# mkstepper.net
KiCad netlist of a schematic drawn in EAGLE
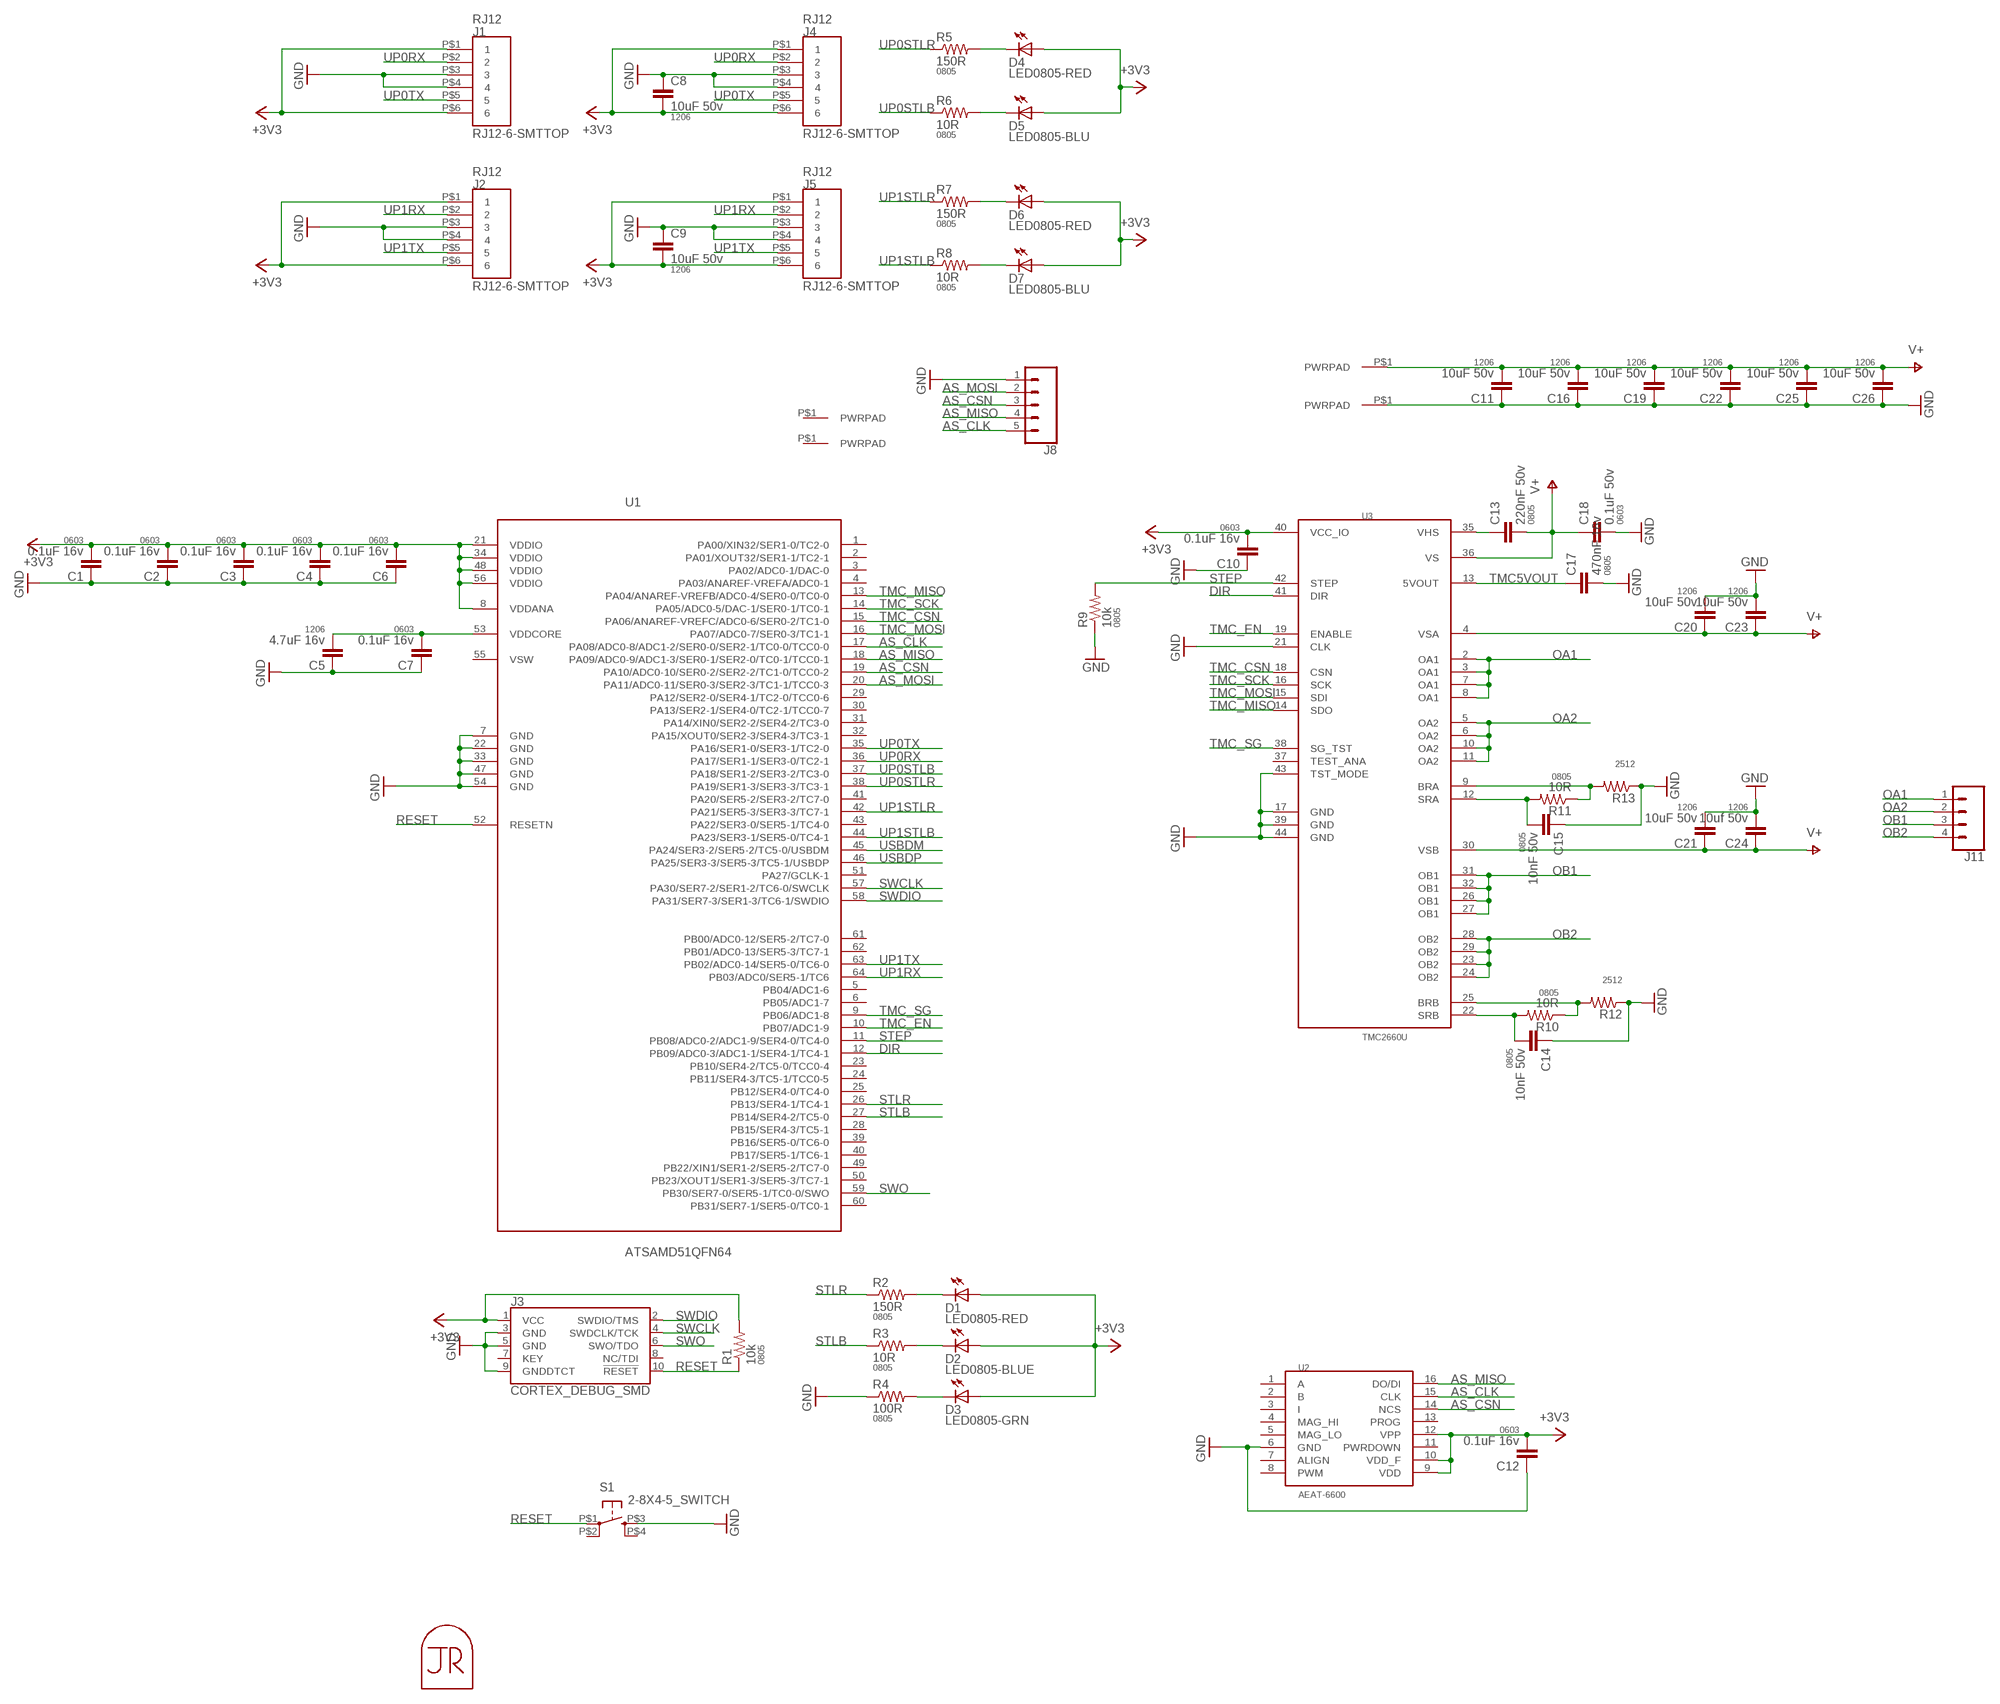
[diagram p0: schematic, sheet 1]

(export (version "E")
  (design (tool "Eeschema 10.0.6"))
  (components
    (comp (ref "C1")
      (value "0.1uF 16v")
      (footprint "eagle-import:0603-CAP")
      (libsource (lib "eagle-import") (part "CAP0603-CAP"))
    )
    (comp (ref "C2")
      (value "0.1uF 16v")
      (footprint "eagle-import:0603-CAP")
      (libsource (lib "eagle-import") (part "CAP0603-CAP"))
    )
    (comp (ref "C3")
      (value "0.1uF 16v")
      (footprint "eagle-import:0603-CAP")
      (libsource (lib "eagle-import") (part "CAP0603-CAP"))
    )
    (comp (ref "C4")
      (value "0.1uF 16v")
      (footprint "eagle-import:0603-CAP")
      (libsource (lib "eagle-import") (part "CAP0603-CAP"))
    )
    (comp (ref "C5")
      (value "4.7uF 16v")
      (footprint "eagle-import:1206")
      (libsource (lib "eagle-import") (part "CAP1206"))
    )
    (comp (ref "C6")
      (value "0.1uF 16v")
      (footprint "eagle-import:0603-CAP")
      (libsource (lib "eagle-import") (part "CAP0603-CAP"))
    )
    (comp (ref "C7")
      (value "0.1uF 16v")
      (footprint "eagle-import:0603-CAP")
      (libsource (lib "eagle-import") (part "CAP0603-CAP"))
    )
    (comp (ref "C8")
      (value "10uF 50v")
      (footprint "eagle-import:1206")
      (libsource (lib "eagle-import") (part "CAP1206"))
    )
    (comp (ref "C9")
      (value "10uF 50v")
      (footprint "eagle-import:1206")
      (libsource (lib "eagle-import") (part "CAP1206"))
    )
    (comp (ref "C10")
      (value "0.1uF 16v")
      (footprint "eagle-import:0603-CAP")
      (libsource (lib "eagle-import") (part "CAP0603-CAP"))
    )
    (comp (ref "C11")
      (value "10uF 50v")
      (footprint "eagle-import:1206")
      (libsource (lib "eagle-import") (part "CAP1206"))
    )
    (comp (ref "C12")
      (value "0.1uF 16v")
      (footprint "eagle-import:0603-CAP")
      (libsource (lib "eagle-import") (part "CAP0603-CAP"))
    )
    (comp (ref "C13")
      (value "220nF 50v")
      (footprint "eagle-import:0805")
      (libsource (lib "eagle-import") (part "CAP0805"))
    )
    (comp (ref "C14")
      (value "10nF 50v")
      (footprint "eagle-import:0805")
      (libsource (lib "eagle-import") (part "CAP0805"))
    )
    (comp (ref "C15")
      (value "10nF 50v")
      (footprint "eagle-import:0805")
      (libsource (lib "eagle-import") (part "CAP0805"))
    )
    (comp (ref "C16")
      (value "10uF 50v")
      (footprint "eagle-import:1206")
      (libsource (lib "eagle-import") (part "CAP1206"))
    )
    (comp (ref "C17")
      (value "470nF 16v")
      (footprint "eagle-import:0805")
      (libsource (lib "eagle-import") (part "CAP0805"))
    )
    (comp (ref "C18")
      (value "0.1uF 50v")
      (footprint "eagle-import:0603-CAP")
      (libsource (lib "eagle-import") (part "CAP0603-CAP"))
    )
    (comp (ref "C19")
      (value "10uF 50v")
      (footprint "eagle-import:1206")
      (libsource (lib "eagle-import") (part "CAP1206"))
    )
    (comp (ref "C20")
      (value "10uF 50v")
      (footprint "eagle-import:1206")
      (libsource (lib "eagle-import") (part "CAP1206"))
    )
    (comp (ref "C21")
      (value "10uF 50v")
      (footprint "eagle-import:1206")
      (libsource (lib "eagle-import") (part "CAP1206"))
    )
    (comp (ref "C22")
      (value "10uF 50v")
      (footprint "eagle-import:1206")
      (libsource (lib "eagle-import") (part "CAP1206"))
    )
    (comp (ref "C23")
      (value "10uF 50v")
      (footprint "eagle-import:1206")
      (libsource (lib "eagle-import") (part "CAP1206"))
    )
    (comp (ref "C24")
      (value "10uf 50v")
      (footprint "eagle-import:1206")
      (libsource (lib "eagle-import") (part "CAP1206"))
    )
    (comp (ref "C25")
      (value "10uF 50v")
      (footprint "eagle-import:1206")
      (libsource (lib "eagle-import") (part "CAP1206"))
    )
    (comp (ref "C26")
      (value "10uF 50v")
      (footprint "eagle-import:1206")
      (libsource (lib "eagle-import") (part "CAP1206"))
    )
    (comp (ref "D1")
      (value "LED0805-RED")
      (footprint "eagle-import:LED0805")
      (libsource (lib "eagle-import") (part "LED0805"))
    )
    (comp (ref "D2")
      (value "LED0805-BLUE")
      (footprint "eagle-import:LED0805")
      (libsource (lib "eagle-import") (part "LED0805"))
    )
    (comp (ref "D3")
      (value "LED0805-GRN")
      (footprint "eagle-import:LED0805")
      (libsource (lib "eagle-import") (part "LED0805"))
    )
    (comp (ref "D4")
      (value "LED0805-RED")
      (footprint "eagle-import:LED0805")
      (libsource (lib "eagle-import") (part "LED0805"))
    )
    (comp (ref "D5")
      (value "LED0805-BLU")
      (footprint "eagle-import:LED0805")
      (libsource (lib "eagle-import") (part "LED0805"))
    )
    (comp (ref "D6")
      (value "LED0805-RED")
      (footprint "eagle-import:LED0805")
      (libsource (lib "eagle-import") (part "LED0805"))
    )
    (comp (ref "D7")
      (value "LED0805-BLU")
      (footprint "eagle-import:LED0805")
      (libsource (lib "eagle-import") (part "LED0805"))
    )
    (comp (ref "J1")
      (value "RJ12-6-SMTTOP")
      (footprint "eagle-import:RJ12-6-SMT-TOPENTRY")
      (libsource (lib "eagle-import") (part "RJ12-6-SMTTOP"))
    )
    (comp (ref "J2")
      (value "RJ12-6-SMTTOP")
      (footprint "eagle-import:RJ12-6-SMT-TOPENTRY")
      (libsource (lib "eagle-import") (part "RJ12-6-SMTTOP"))
    )
    (comp (ref "J3")
      (value "CORTEX_DEBUG_SMD")
      (footprint "eagle-import:SAMTECH_FTSH-105-01")
      (libsource (lib "eagle-import") (part "CORTEX_DEBUG_SMD"))
    )
    (comp (ref "J4")
      (value "RJ12-6-SMTTOP")
      (footprint "eagle-import:RJ12-6-SMT-TOPENTRY")
      (libsource (lib "eagle-import") (part "RJ12-6-SMTTOP"))
    )
    (comp (ref "J5")
      (value "RJ12-6-SMTTOP")
      (footprint "eagle-import:RJ12-6-SMT-TOPENTRY")
      (libsource (lib "eagle-import") (part "RJ12-6-SMTTOP"))
    )
    (comp (ref "J6")
      (value "PWRPADM3")
      (footprint "eagle-import:PWRPAD_3-25MM")
      (libsource (lib "eagle-import") (part "PWRPADM3"))
    )
    (comp (ref "J7")
      (value "PWRPADM3")
      (footprint "eagle-import:PWRPAD_3-25MM")
      (libsource (lib "eagle-import") (part "PWRPADM3"))
    )
    (comp (ref "J8")
      (value "CONN_05NO_SILK")
      (footprint "eagle-import:1X05_NO_SILK")
      (libsource (lib "eagle-import") (part "CONN_05NO_SILK"))
    )
    (comp (ref "J9")
      (value "PWRPAD")
      (footprint "eagle-import:PWRPAD_M3-PEM-MOUNT")
      (libsource (lib "eagle-import") (part "PWRPAD"))
    )
    (comp (ref "J10")
      (value "PWRPAD")
      (footprint "eagle-import:PWRPAD_M3-PEM-MOUNT")
      (libsource (lib "eagle-import") (part "PWRPAD"))
    )
    (comp (ref "J11")
      (value "CONN_04LONGPADS")
      (footprint "eagle-import:1X04_LONGPADS")
      (libsource (lib "eagle-import") (part "CONN_04LONGPADS"))
    )
    (comp (ref "MP1")
      (value "JRTOMBSTONE")
      (footprint "eagle-import:JRTOMBSTONE")
      (libsource (lib "eagle-import") (part "JRTOMBSTONE"))
    )
    (comp (ref "R1")
      (value "10k")
      (footprint "eagle-import:0805")
      (libsource (lib "eagle-import") (part "RESISTOR0805-RES"))
    )
    (comp (ref "R2")
      (value "150R")
      (footprint "eagle-import:0805")
      (libsource (lib "eagle-import") (part "RESISTOR0805-RES"))
    )
    (comp (ref "R3")
      (value "10R")
      (footprint "eagle-import:0805")
      (libsource (lib "eagle-import") (part "RESISTOR0805-RES"))
    )
    (comp (ref "R4")
      (value "100R")
      (footprint "eagle-import:0805")
      (libsource (lib "eagle-import") (part "RESISTOR0805-RES"))
    )
    (comp (ref "R5")
      (value "150R")
      (footprint "eagle-import:0805")
      (libsource (lib "eagle-import") (part "RESISTOR0805-RES"))
    )
    (comp (ref "R6")
      (value "10R")
      (footprint "eagle-import:0805")
      (libsource (lib "eagle-import") (part "RESISTOR0805-RES"))
    )
    (comp (ref "R7")
      (value "150R")
      (footprint "eagle-import:0805")
      (libsource (lib "eagle-import") (part "RESISTOR0805-RES"))
    )
    (comp (ref "R8")
      (value "10R")
      (footprint "eagle-import:0805")
      (libsource (lib "eagle-import") (part "RESISTOR0805-RES"))
    )
    (comp (ref "R9")
      (value "10k")
      (footprint "eagle-import:0805")
      (libsource (lib "eagle-import") (part "RESISTOR0805-RES"))
    )
    (comp (ref "R10")
      (value "10R")
      (footprint "eagle-import:0805")
      (libsource (lib "eagle-import") (part "RESISTOR0805-RES"))
    )
    (comp (ref "R11")
      (value "10R")
      (footprint "eagle-import:0805")
      (libsource (lib "eagle-import") (part "RESISTOR0805-RES"))
    )
    (comp (ref "R12")
      (value "RESISTOR2512")
      (footprint "eagle-import:R2512")
      (libsource (lib "eagle-import") (part "RESISTOR2512"))
    )
    (comp (ref "R13")
      (value "RESISTOR2512")
      (footprint "eagle-import:R2512")
      (libsource (lib "eagle-import") (part "RESISTOR2512"))
    )
    (comp (ref "S1")
      (value "2-8X4-5_SWITCH")
      (footprint "eagle-import:TACT-SWITCH-KMR6")
      (libsource (lib "eagle-import") (part "2-8X4-5_SWITCH"))
    )
    (comp (ref "U1")
      (value "ATSAMD51QFN64")
      (footprint "eagle-import:QFN-64-9X9MM")
      (libsource (lib "eagle-import") (part "ATSAMD51QFN64"))
    )
    (comp (ref "U2")
      (value "AEAT-6600")
      (footprint "eagle-import:TSSOP16")
      (libsource (lib "eagle-import") (part "AEAT-6600"))
    )
    (comp (ref "U3")
      (value "TMC2660U")
      (footprint "eagle-import:TQFP44")
      (libsource (lib "eagle-import") (part "TMC2660U"))
    )
  )
  (nets
    (net (code "1") (name "+3V3") (class "Default")
      (node (ref "C1") (pin "2") (pinfunction "2_2") (pintype "passive"))
      (node (ref "C10") (pin "2") (pinfunction "2_2") (pintype "passive"))
      (node (ref "C12") (pin "2") (pinfunction "2_2") (pintype "passive"))
      (node (ref "C2") (pin "2") (pinfunction "2_2") (pintype "passive"))
      (node (ref "C3") (pin "2") (pinfunction "2_2") (pintype "passive"))
      (node (ref "C4") (pin "2") (pinfunction "2_2") (pintype "passive"))
      (node (ref "C6") (pin "2") (pinfunction "2_2") (pintype "passive"))
      (node (ref "C8") (pin "2") (pinfunction "2_2") (pintype "passive"))
      (node (ref "C9") (pin "2") (pinfunction "2_2") (pintype "passive"))
      (node (ref "D1") (pin "1") (pinfunction "A_1") (pintype "passive"))
      (node (ref "D2") (pin "1") (pinfunction "A_1") (pintype "passive"))
      (node (ref "D3") (pin "1") (pinfunction "A_1") (pintype "passive"))
      (node (ref "D4") (pin "1") (pinfunction "A_1") (pintype "passive"))
      (node (ref "D5") (pin "1") (pinfunction "A_1") (pintype "passive"))
      (node (ref "D6") (pin "1") (pinfunction "A_1") (pintype "passive"))
      (node (ref "D7") (pin "1") (pinfunction "A_1") (pintype "passive"))
      (node (ref "J1") (pin "P$1") (pinfunction "1_P$1") (pintype "bidirectional"))
      (node (ref "J1") (pin "P$6") (pinfunction "6_P$6") (pintype "bidirectional"))
      (node (ref "J2") (pin "P$1") (pinfunction "1_P$1") (pintype "bidirectional"))
      (node (ref "J2") (pin "P$6") (pinfunction "6_P$6") (pintype "bidirectional"))
      (node (ref "J3") (pin "1") (pinfunction "VCC_1") (pintype "bidirectional"))
      (node (ref "J4") (pin "P$1") (pinfunction "1_P$1") (pintype "bidirectional"))
      (node (ref "J4") (pin "P$6") (pinfunction "6_P$6") (pintype "bidirectional"))
      (node (ref "J5") (pin "P$1") (pinfunction "1_P$1") (pintype "bidirectional"))
      (node (ref "J5") (pin "P$6") (pinfunction "6_P$6") (pintype "bidirectional"))
      (node (ref "R1") (pin "2") (pinfunction "2_2") (pintype "passive"))
      (node (ref "U1") (pin "21") (pinfunction "VDDIO_21") (pintype "bidirectional"))
      (node (ref "U1") (pin "34") (pinfunction "VDDIO_34") (pintype "bidirectional"))
      (node (ref "U1") (pin "48") (pinfunction "VDDIO_48") (pintype "bidirectional"))
      (node (ref "U1") (pin "56") (pinfunction "VDDIO_56") (pintype "bidirectional"))
      (node (ref "U1") (pin "8") (pinfunction "VDDANA_8") (pintype "bidirectional"))
      (node (ref "U2") (pin "10") (pinfunction "VDD_F_10") (pintype "bidirectional"))
      (node (ref "U2") (pin "12") (pinfunction "VPP_12") (pintype "bidirectional"))
      (node (ref "U2") (pin "9") (pinfunction "VDD_9") (pintype "bidirectional"))
      (node (ref "U3") (pin "40") (pinfunction "VCC_IO_40") (pintype "bidirectional"))
    )
    (net (code "2") (name "/AS_CLK") (class "Default")
      (node (ref "J8") (pin "5") (pinfunction "5_5") (pintype "passive"))
      (node (ref "U1") (pin "17") (pinfunction "PA08/ADC0-8/ADC1-2/SER0-0/SER2-1/TC0-0/TCC0-0_17") (pintype "bidirectional"))
      (node (ref "U2") (pin "15") (pinfunction "CLK_15") (pintype "bidirectional"))
    )
    (net (code "3") (name "/AS_CSN") (class "Default")
      (node (ref "J8") (pin "3") (pinfunction "3_3") (pintype "passive"))
      (node (ref "U1") (pin "19") (pinfunction "PA10/ADC0-10/SER0-2/SER2-2/TC1-0/TCC0-2_19") (pintype "bidirectional"))
      (node (ref "U2") (pin "14") (pinfunction "NCS_14") (pintype "bidirectional"))
    )
    (net (code "4") (name "/AS_MISO") (class "Default")
      (node (ref "J8") (pin "4") (pinfunction "4_4") (pintype "passive"))
      (node (ref "U1") (pin "18") (pinfunction "PA09/ADC0-9/ADC1-3/SER0-1/SER2-0/TC0-1/TCC0-1_18") (pintype "bidirectional"))
      (node (ref "U2") (pin "16") (pinfunction "DO/DI_16") (pintype "bidirectional"))
    )
    (net (code "5") (name "/AS_MOSI") (class "Default")
      (node (ref "J8") (pin "2") (pinfunction "2_2") (pintype "passive"))
      (node (ref "U1") (pin "20") (pinfunction "PA11/ADC0-11/SER0-3/SER2-3/TC1-1/TCC0-3_20") (pintype "bidirectional"))
    )
    (net (code "6") (name "/DIR") (class "Default")
      (node (ref "U1") (pin "12") (pinfunction "PB09/ADC0-3/ADC1-1/SER4-1/TC4-1_12") (pintype "bidirectional"))
      (node (ref "U3") (pin "41") (pinfunction "DIR_41") (pintype "bidirectional"))
    )
    (net (code "7") (name "/OA1") (class "Default")
      (node (ref "J11") (pin "1") (pinfunction "1_1") (pintype "passive"))
      (node (ref "U3") (pin "2") (pinfunction "OA1_2") (pintype "bidirectional"))
      (node (ref "U3") (pin "3") (pinfunction "OA1_3") (pintype "bidirectional"))
      (node (ref "U3") (pin "7") (pinfunction "OA1_7") (pintype "bidirectional"))
      (node (ref "U3") (pin "8") (pinfunction "OA1_8") (pintype "bidirectional"))
    )
    (net (code "8") (name "/OA2") (class "Default")
      (node (ref "J11") (pin "2") (pinfunction "2_2") (pintype "passive"))
      (node (ref "U3") (pin "10") (pinfunction "OA2_10") (pintype "bidirectional"))
      (node (ref "U3") (pin "11") (pinfunction "OA2_11") (pintype "bidirectional"))
      (node (ref "U3") (pin "5") (pinfunction "OA2_5") (pintype "bidirectional"))
      (node (ref "U3") (pin "6") (pinfunction "OA2_6") (pintype "bidirectional"))
    )
    (net (code "9") (name "/OB1") (class "Default")
      (node (ref "J11") (pin "3") (pinfunction "3_3") (pintype "passive"))
      (node (ref "U3") (pin "26") (pinfunction "OB1_26") (pintype "bidirectional"))
      (node (ref "U3") (pin "27") (pinfunction "OB1_27") (pintype "bidirectional"))
      (node (ref "U3") (pin "31") (pinfunction "OB1_31") (pintype "bidirectional"))
      (node (ref "U3") (pin "32") (pinfunction "OB1_32") (pintype "bidirectional"))
    )
    (net (code "10") (name "/OB2") (class "Default")
      (node (ref "J11") (pin "4") (pinfunction "4_4") (pintype "passive"))
      (node (ref "U3") (pin "23") (pinfunction "OB2_23") (pintype "bidirectional"))
      (node (ref "U3") (pin "24") (pinfunction "OB2_24") (pintype "bidirectional"))
      (node (ref "U3") (pin "28") (pinfunction "OB2_28") (pintype "bidirectional"))
      (node (ref "U3") (pin "29") (pinfunction "OB2_29") (pintype "bidirectional"))
    )
    (net (code "11") (name "/RESET") (class "Default")
      (node (ref "J3") (pin "10") (pinfunction "~{RESET}_10") (pintype "bidirectional"))
      (node (ref "R1") (pin "1") (pinfunction "1_1") (pintype "passive"))
      (node (ref "S1") (pin "P$1") (pinfunction "P_P$1") (pintype "passive"))
      (node (ref "U1") (pin "52") (pinfunction "RESETN_52") (pintype "bidirectional"))
    )
    (net (code "12") (name "/STEP") (class "Default")
      (node (ref "R9") (pin "2") (pinfunction "2_2") (pintype "passive"))
      (node (ref "U1") (pin "11") (pinfunction "PB08/ADC0-2/ADC1-9/SER4-0/TC4-0_11") (pintype "bidirectional"))
      (node (ref "U3") (pin "42") (pinfunction "STEP_42") (pintype "bidirectional"))
    )
    (net (code "13") (name "/STLB") (class "Default")
      (node (ref "R3") (pin "1") (pinfunction "1_1") (pintype "passive"))
      (node (ref "U1") (pin "27") (pinfunction "PB14/SER4-2/TC5-0_27") (pintype "bidirectional"))
    )
    (net (code "14") (name "/STLR") (class "Default")
      (node (ref "R2") (pin "1") (pinfunction "1_1") (pintype "passive"))
      (node (ref "U1") (pin "26") (pinfunction "PB13/SER4-1/TC4-1_26") (pintype "bidirectional"))
    )
    (net (code "15") (name "/SWCLK") (class "Default")
      (node (ref "J3") (pin "4") (pinfunction "SWDCLK/TCK_4") (pintype "bidirectional"))
      (node (ref "U1") (pin "57") (pinfunction "PA30/SER7-2/SER1-2/TC6-0/SWCLK_57") (pintype "bidirectional"))
    )
    (net (code "16") (name "/SWDIO") (class "Default")
      (node (ref "J3") (pin "2") (pinfunction "SWDIO/TMS_2") (pintype "bidirectional"))
      (node (ref "U1") (pin "58") (pinfunction "PA31/SER7-3/SER1-3/TC6-1/SWDIO_58") (pintype "bidirectional"))
    )
    (net (code "17") (name "/SWO") (class "Default")
      (node (ref "J3") (pin "6") (pinfunction "SWO/TDO_6") (pintype "bidirectional"))
      (node (ref "U1") (pin "59") (pinfunction "PB30/SER7-0/SER5-1/TC0-0/SWO_59") (pintype "bidirectional"))
    )
    (net (code "18") (name "/TMC5VOUT") (class "Default")
      (node (ref "C17") (pin "1") (pinfunction "1_1") (pintype "passive"))
      (node (ref "U3") (pin "13") (pinfunction "5VOUT_13") (pintype "bidirectional"))
    )
    (net (code "19") (name "/TMC_CSN") (class "Default")
      (node (ref "U1") (pin "15") (pinfunction "PA06/ANAREF-VREFC/ADC0-6/SER0-2/TC1-0_15") (pintype "bidirectional"))
      (node (ref "U3") (pin "18") (pinfunction "CSN_18") (pintype "bidirectional"))
    )
    (net (code "20") (name "/TMC_EN") (class "Default")
      (node (ref "U1") (pin "10") (pinfunction "PB07/ADC1-9_10") (pintype "bidirectional"))
      (node (ref "U3") (pin "19") (pinfunction "ENABLE_19") (pintype "bidirectional"))
    )
    (net (code "21") (name "/TMC_MISO") (class "Default")
      (node (ref "U1") (pin "13") (pinfunction "PA04/ANAREF-VREFB/ADC0-4/SER0-0/TC0-0_13") (pintype "bidirectional"))
      (node (ref "U3") (pin "14") (pinfunction "SDO_14") (pintype "bidirectional"))
    )
    (net (code "22") (name "/TMC_MOSI") (class "Default")
      (node (ref "U1") (pin "16") (pinfunction "PA07/ADC0-7/SER0-3/TC1-1_16") (pintype "bidirectional"))
      (node (ref "U3") (pin "15") (pinfunction "SDI_15") (pintype "bidirectional"))
    )
    (net (code "23") (name "/TMC_SCK") (class "Default")
      (node (ref "U1") (pin "14") (pinfunction "PA05/ADC0-5/DAC-1/SER0-1/TC0-1_14") (pintype "bidirectional"))
      (node (ref "U3") (pin "16") (pinfunction "SCK_16") (pintype "bidirectional"))
    )
    (net (code "24") (name "/TMC_SG") (class "Default")
      (node (ref "U1") (pin "9") (pinfunction "PB06/ADC1-8_9") (pintype "bidirectional"))
      (node (ref "U3") (pin "38") (pinfunction "SG_TST_38") (pintype "bidirectional"))
    )
    (net (code "25") (name "/UP0RX") (class "Default")
      (node (ref "J1") (pin "P$2") (pinfunction "2_P$2") (pintype "bidirectional"))
      (node (ref "J4") (pin "P$2") (pinfunction "2_P$2") (pintype "bidirectional"))
      (node (ref "U1") (pin "36") (pinfunction "PA17/SER1-1/SER3-0/TC2-1_36") (pintype "bidirectional"))
    )
    (net (code "26") (name "/UP0STLB") (class "Default")
      (node (ref "R6") (pin "1") (pinfunction "1_1") (pintype "passive"))
      (node (ref "U1") (pin "37") (pinfunction "PA18/SER1-2/SER3-2/TC3-0_37") (pintype "bidirectional"))
    )
    (net (code "27") (name "/UP0STLR") (class "Default")
      (node (ref "R5") (pin "1") (pinfunction "1_1") (pintype "passive"))
      (node (ref "U1") (pin "38") (pinfunction "PA19/SER1-3/SER3-3/TC3-1_38") (pintype "bidirectional"))
    )
    (net (code "28") (name "/UP0TX") (class "Default")
      (node (ref "J1") (pin "P$5") (pinfunction "5_P$5") (pintype "bidirectional"))
      (node (ref "J4") (pin "P$5") (pinfunction "5_P$5") (pintype "bidirectional"))
      (node (ref "U1") (pin "35") (pinfunction "PA16/SER1-0/SER3-1/TC2-0_35") (pintype "bidirectional"))
    )
    (net (code "29") (name "/UP1RX") (class "Default")
      (node (ref "J2") (pin "P$2") (pinfunction "2_P$2") (pintype "bidirectional"))
      (node (ref "J5") (pin "P$2") (pinfunction "2_P$2") (pintype "bidirectional"))
      (node (ref "U1") (pin "64") (pinfunction "PB03/ADC0/SER5-1/TC6_64") (pintype "bidirectional"))
    )
    (net (code "30") (name "/UP1STLB") (class "Default")
      (node (ref "R8") (pin "1") (pinfunction "1_1") (pintype "passive"))
      (node (ref "U1") (pin "44") (pinfunction "PA23/SER3-1/SER5-0/TC4-1_44") (pintype "bidirectional"))
    )
    (net (code "31") (name "/UP1STLR") (class "Default")
      (node (ref "R7") (pin "1") (pinfunction "1_1") (pintype "passive"))
      (node (ref "U1") (pin "42") (pinfunction "PA21/SER5-3/SER3-3/TC7-1_42") (pintype "bidirectional"))
    )
    (net (code "32") (name "/UP1TX") (class "Default")
      (node (ref "J2") (pin "P$5") (pinfunction "5_P$5") (pintype "bidirectional"))
      (node (ref "J5") (pin "P$5") (pinfunction "5_P$5") (pintype "bidirectional"))
      (node (ref "U1") (pin "63") (pinfunction "PB02/ADC0-14/SER5-0/TC6-0_63") (pintype "bidirectional"))
    )
    (net (code "33") (name "/USBDM") (class "Default")
      (node (ref "U1") (pin "45") (pinfunction "PA24/SER3-2/SER5-2/TC5-0/USBDM_45") (pintype "bidirectional"))
    )
    (net (code "34") (name "/USBDP") (class "Default")
      (node (ref "U1") (pin "46") (pinfunction "PA25/SER3-3/SER5-3/TC5-1/USBDP_46") (pintype "bidirectional"))
    )
    (net (code "35") (name "GND") (class "Default")
      (node (ref "C1") (pin "1") (pinfunction "1_1") (pintype "passive"))
      (node (ref "C10") (pin "1") (pinfunction "1_1") (pintype "passive"))
      (node (ref "C11") (pin "1") (pinfunction "1_1") (pintype "passive"))
      (node (ref "C12") (pin "1") (pinfunction "1_1") (pintype "passive"))
      (node (ref "C14") (pin "1") (pinfunction "1_1") (pintype "passive"))
      (node (ref "C15") (pin "1") (pinfunction "1_1") (pintype "passive"))
      (node (ref "C16") (pin "1") (pinfunction "1_1") (pintype "passive"))
      (node (ref "C17") (pin "2") (pinfunction "2_2") (pintype "passive"))
      (node (ref "C18") (pin "2") (pinfunction "2_2") (pintype "passive"))
      (node (ref "C19") (pin "1") (pinfunction "1_1") (pintype "passive"))
      (node (ref "C2") (pin "1") (pinfunction "1_1") (pintype "passive"))
      (node (ref "C20") (pin "2") (pinfunction "2_2") (pintype "passive"))
      (node (ref "C21") (pin "2") (pinfunction "2_2") (pintype "passive"))
      (node (ref "C22") (pin "1") (pinfunction "1_1") (pintype "passive"))
      (node (ref "C23") (pin "2") (pinfunction "2_2") (pintype "passive"))
      (node (ref "C24") (pin "2") (pinfunction "2_2") (pintype "passive"))
      (node (ref "C25") (pin "1") (pinfunction "1_1") (pintype "passive"))
      (node (ref "C26") (pin "1") (pinfunction "1_1") (pintype "passive"))
      (node (ref "C3") (pin "1") (pinfunction "1_1") (pintype "passive"))
      (node (ref "C4") (pin "1") (pinfunction "1_1") (pintype "passive"))
      (node (ref "C5") (pin "1") (pinfunction "1_1") (pintype "passive"))
      (node (ref "C6") (pin "1") (pinfunction "1_1") (pintype "passive"))
      (node (ref "C7") (pin "1") (pinfunction "1_1") (pintype "passive"))
      (node (ref "C8") (pin "1") (pinfunction "1_1") (pintype "passive"))
      (node (ref "C9") (pin "1") (pinfunction "1_1") (pintype "passive"))
      (node (ref "J1") (pin "P$3") (pinfunction "3_P$3") (pintype "bidirectional"))
      (node (ref "J1") (pin "P$4") (pinfunction "4_P$4") (pintype "bidirectional"))
      (node (ref "J10") (pin "P$1") (pinfunction "PWRPAD_P$1") (pintype "bidirectional"))
      (node (ref "J2") (pin "P$3") (pinfunction "3_P$3") (pintype "bidirectional"))
      (node (ref "J2") (pin "P$4") (pinfunction "4_P$4") (pintype "bidirectional"))
      (node (ref "J3") (pin "3") (pinfunction "GND_3") (pintype "bidirectional"))
      (node (ref "J3") (pin "5") (pinfunction "GND_5") (pintype "bidirectional"))
      (node (ref "J3") (pin "9") (pinfunction "GNDDTCT_9") (pintype "bidirectional"))
      (node (ref "J4") (pin "P$3") (pinfunction "3_P$3") (pintype "bidirectional"))
      (node (ref "J4") (pin "P$4") (pinfunction "4_P$4") (pintype "bidirectional"))
      (node (ref "J5") (pin "P$3") (pinfunction "3_P$3") (pintype "bidirectional"))
      (node (ref "J5") (pin "P$4") (pinfunction "4_P$4") (pintype "bidirectional"))
      (node (ref "J8") (pin "1") (pinfunction "1_1") (pintype "passive"))
      (node (ref "R12") (pin "1") (pinfunction "1_1") (pintype "passive"))
      (node (ref "R13") (pin "1") (pinfunction "1_1") (pintype "passive"))
      (node (ref "R4") (pin "1") (pinfunction "1_1") (pintype "passive"))
      (node (ref "R9") (pin "1") (pinfunction "1_1") (pintype "passive"))
      (node (ref "S1") (pin "P$3") (pinfunction "S_P$3") (pintype "passive"))
      (node (ref "U1") (pin "22") (pinfunction "GND_22") (pintype "bidirectional"))
      (node (ref "U1") (pin "33") (pinfunction "GND_33") (pintype "bidirectional"))
      (node (ref "U1") (pin "47") (pinfunction "GND_47") (pintype "bidirectional"))
      (node (ref "U1") (pin "54") (pinfunction "GND_54") (pintype "bidirectional"))
      (node (ref "U1") (pin "7") (pinfunction "GND_7") (pintype "bidirectional"))
      (node (ref "U2") (pin "6") (pinfunction "GND_6") (pintype "bidirectional"))
      (node (ref "U3") (pin "17") (pinfunction "GND_17") (pintype "bidirectional"))
      (node (ref "U3") (pin "21") (pinfunction "CLK_21") (pintype "bidirectional"))
      (node (ref "U3") (pin "39") (pinfunction "GND_39") (pintype "bidirectional"))
      (node (ref "U3") (pin "43") (pinfunction "TST_MODE_43") (pintype "bidirectional"))
      (node (ref "U3") (pin "44") (pinfunction "GND_44") (pintype "bidirectional"))
    )
    (net (code "36") (name "Net-(D1-C)") (class "Default")
      (node (ref "D1") (pin "2") (pinfunction "C_2") (pintype "passive"))
      (node (ref "R2") (pin "2") (pinfunction "2_2") (pintype "passive"))
    )
    (net (code "37") (name "Net-(D2-C)") (class "Default")
      (node (ref "D2") (pin "2") (pinfunction "C_2") (pintype "passive"))
      (node (ref "R3") (pin "2") (pinfunction "2_2") (pintype "passive"))
    )
    (net (code "38") (name "Net-(D3-C)") (class "Default")
      (node (ref "D3") (pin "2") (pinfunction "C_2") (pintype "passive"))
      (node (ref "R4") (pin "2") (pinfunction "2_2") (pintype "passive"))
    )
    (net (code "39") (name "Net-(D4-C)") (class "Default")
      (node (ref "D4") (pin "2") (pinfunction "C_2") (pintype "passive"))
      (node (ref "R5") (pin "2") (pinfunction "2_2") (pintype "passive"))
    )
    (net (code "40") (name "Net-(D5-C)") (class "Default")
      (node (ref "D5") (pin "2") (pinfunction "C_2") (pintype "passive"))
      (node (ref "R6") (pin "2") (pinfunction "2_2") (pintype "passive"))
    )
    (net (code "41") (name "Net-(D6-C)") (class "Default")
      (node (ref "D6") (pin "2") (pinfunction "C_2") (pintype "passive"))
      (node (ref "R7") (pin "2") (pinfunction "2_2") (pintype "passive"))
    )
    (net (code "42") (name "Net-(D7-C)") (class "Default")
      (node (ref "D7") (pin "2") (pinfunction "C_2") (pintype "passive"))
      (node (ref "R8") (pin "2") (pinfunction "2_2") (pintype "passive"))
    )
    (net (code "43") (name "Net-(U1-VDDCORE)") (class "Default")
      (node (ref "C5") (pin "2") (pinfunction "2_2") (pintype "passive"))
      (node (ref "C7") (pin "2") (pinfunction "2_2") (pintype "passive"))
      (node (ref "U1") (pin "53") (pinfunction "VDDCORE_53") (pintype "bidirectional"))
    )
    (net (code "44") (name "Net-(U3-BRA)") (class "Default")
      (node (ref "R11") (pin "1") (pinfunction "1_1") (pintype "passive"))
      (node (ref "R13") (pin "2") (pinfunction "2_2") (pintype "passive"))
      (node (ref "U3") (pin "9") (pinfunction "BRA_9") (pintype "bidirectional"))
    )
    (net (code "45") (name "Net-(U3-BRB)") (class "Default")
      (node (ref "R10") (pin "1") (pinfunction "1_1") (pintype "passive"))
      (node (ref "R12") (pin "2") (pinfunction "2_2") (pintype "passive"))
      (node (ref "U3") (pin "25") (pinfunction "BRB_25") (pintype "bidirectional"))
    )
    (net (code "46") (name "Net-(U3-SRA)") (class "Default")
      (node (ref "C15") (pin "2") (pinfunction "2_2") (pintype "passive"))
      (node (ref "R11") (pin "2") (pinfunction "2_2") (pintype "passive"))
      (node (ref "U3") (pin "12") (pinfunction "SRA_12") (pintype "bidirectional"))
    )
    (net (code "47") (name "Net-(U3-SRB)") (class "Default")
      (node (ref "C14") (pin "2") (pinfunction "2_2") (pintype "passive"))
      (node (ref "R10") (pin "2") (pinfunction "2_2") (pintype "passive"))
      (node (ref "U3") (pin "22") (pinfunction "SRB_22") (pintype "bidirectional"))
    )
    (net (code "48") (name "Net-(U3-VHS)") (class "Default")
      (node (ref "C13") (pin "1") (pinfunction "1_1") (pintype "passive"))
      (node (ref "U3") (pin "35") (pinfunction "VHS_35") (pintype "bidirectional"))
    )
    (net (code "49") (name "V+") (class "Default")
      (node (ref "C11") (pin "2") (pinfunction "2_2") (pintype "passive"))
      (node (ref "C13") (pin "2") (pinfunction "2_2") (pintype "passive"))
      (node (ref "C16") (pin "2") (pinfunction "2_2") (pintype "passive"))
      (node (ref "C18") (pin "1") (pinfunction "1_1") (pintype "passive"))
      (node (ref "C19") (pin "2") (pinfunction "2_2") (pintype "passive"))
      (node (ref "C20") (pin "1") (pinfunction "1_1") (pintype "passive"))
      (node (ref "C21") (pin "1") (pinfunction "1_1") (pintype "passive"))
      (node (ref "C22") (pin "2") (pinfunction "2_2") (pintype "passive"))
      (node (ref "C23") (pin "1") (pinfunction "1_1") (pintype "passive"))
      (node (ref "C24") (pin "1") (pinfunction "1_1") (pintype "passive"))
      (node (ref "C25") (pin "2") (pinfunction "2_2") (pintype "passive"))
      (node (ref "C26") (pin "2") (pinfunction "2_2") (pintype "passive"))
      (node (ref "J9") (pin "P$1") (pinfunction "PWRPAD_P$1") (pintype "bidirectional"))
      (node (ref "U3") (pin "30") (pinfunction "VSB_30") (pintype "bidirectional"))
      (node (ref "U3") (pin "36") (pinfunction "VS_36") (pintype "bidirectional"))
      (node (ref "U3") (pin "4") (pinfunction "VSA_4") (pintype "bidirectional"))
    )
    (net (code "50") (name "unconnected-(J3-KEY-Pad7)") (class "Default")
      (node (ref "J3") (pin "7") (pinfunction "KEY_7") (pintype "bidirectional"))
    )
    (net (code "51") (name "unconnected-(J3-NC{slash}TDI-Pad8)") (class "Default")
      (node (ref "J3") (pin "8") (pinfunction "NC/TDI_8") (pintype "bidirectional"))
    )
    (net (code "52") (name "unconnected-(J6-PWRPAD-PadP$1)") (class "Default")
      (node (ref "J6") (pin "P$1") (pinfunction "PWRPAD_P$1") (pintype "bidirectional"))
    )
    (net (code "53") (name "unconnected-(J7-PWRPAD-PadP$1)") (class "Default")
      (node (ref "J7") (pin "P$1") (pinfunction "PWRPAD_P$1") (pintype "bidirectional"))
    )
    (net (code "54") (name "unconnected-(S1-P1-PadP$2)") (class "Default")
      (node (ref "S1") (pin "P$2") (pinfunction "P1_P$2") (pintype "passive"))
    )
    (net (code "55") (name "unconnected-(S1-S1-PadP$4)") (class "Default")
      (node (ref "S1") (pin "P$4") (pinfunction "S1_P$4") (pintype "passive"))
    )
    (net (code "56") (name "unconnected-(U1-PA00{slash}XIN32{slash}SER1-0{slash}TC2-0-Pad1)") (class "Default")
      (node (ref "U1") (pin "1") (pinfunction "PA00/XIN32/SER1-0/TC2-0_1") (pintype "bidirectional"))
    )
    (net (code "57") (name "unconnected-(U1-PA01{slash}XOUT32{slash}SER1-1{slash}TC2-1-Pad2)") (class "Default")
      (node (ref "U1") (pin "2") (pinfunction "PA01/XOUT32/SER1-1/TC2-1_2") (pintype "bidirectional"))
    )
    (net (code "58") (name "unconnected-(U1-PA02{slash}ADC0-1{slash}DAC-0-Pad3)") (class "Default")
      (node (ref "U1") (pin "3") (pinfunction "PA02/ADC0-1/DAC-0_3") (pintype "bidirectional"))
    )
    (net (code "59") (name "unconnected-(U1-PA03{slash}ANAREF-VREFA{slash}ADC0-1-Pad4)") (class "Default")
      (node (ref "U1") (pin "4") (pinfunction "PA03/ANAREF-VREFA/ADC0-1_4") (pintype "bidirectional"))
    )
    (net (code "60") (name "unconnected-(U1-PA12{slash}SER2-0{slash}SER4-1{slash}TC2-0{slash}TCC0-6-Pad29)") (class "Default")
      (node (ref "U1") (pin "29") (pinfunction "PA12/SER2-0/SER4-1/TC2-0/TCC0-6_29") (pintype "bidirectional"))
    )
    (net (code "61") (name "unconnected-(U1-PA13{slash}SER2-1{slash}SER4-0{slash}TC2-1{slash}TCC0-7-Pad30)") (class "Default")
      (node (ref "U1") (pin "30") (pinfunction "PA13/SER2-1/SER4-0/TC2-1/TCC0-7_30") (pintype "bidirectional"))
    )
    (net (code "62") (name "unconnected-(U1-PA14{slash}XIN0{slash}SER2-2{slash}SER4-2{slash}TC3-0-Pad31)") (class "Default")
      (node (ref "U1") (pin "31") (pinfunction "PA14/XIN0/SER2-2/SER4-2/TC3-0_31") (pintype "bidirectional"))
    )
    (net (code "63") (name "unconnected-(U1-PA15{slash}XOUT0{slash}SER2-3{slash}SER4-3{slash}TC3-1-Pad32)") (class "Default")
      (node (ref "U1") (pin "32") (pinfunction "PA15/XOUT0/SER2-3/SER4-3/TC3-1_32") (pintype "bidirectional"))
    )
    (net (code "64") (name "unconnected-(U1-PA20{slash}SER5-2{slash}SER3-2{slash}TC7-0-Pad41)") (class "Default")
      (node (ref "U1") (pin "41") (pinfunction "PA20/SER5-2/SER3-2/TC7-0_41") (pintype "bidirectional"))
    )
    (net (code "65") (name "unconnected-(U1-PA22{slash}SER3-0{slash}SER5-1{slash}TC4-0-Pad43)") (class "Default")
      (node (ref "U1") (pin "43") (pinfunction "PA22/SER3-0/SER5-1/TC4-0_43") (pintype "bidirectional"))
    )
    (net (code "66") (name "unconnected-(U1-PA27{slash}GCLK-1-Pad51)") (class "Default")
      (node (ref "U1") (pin "51") (pinfunction "PA27/GCLK-1_51") (pintype "bidirectional"))
    )
    (net (code "67") (name "unconnected-(U1-PB00{slash}ADC0-12{slash}SER5-2{slash}TC7-0-Pad61)") (class "Default")
      (node (ref "U1") (pin "61") (pinfunction "PB00/ADC0-12/SER5-2/TC7-0_61") (pintype "bidirectional"))
    )
    (net (code "68") (name "unconnected-(U1-PB01{slash}ADC0-13{slash}SER5-3{slash}TC7-1-Pad62)") (class "Default")
      (node (ref "U1") (pin "62") (pinfunction "PB01/ADC0-13/SER5-3/TC7-1_62") (pintype "bidirectional"))
    )
    (net (code "69") (name "unconnected-(U1-PB04{slash}ADC1-6-Pad5)") (class "Default")
      (node (ref "U1") (pin "5") (pinfunction "PB04/ADC1-6_5") (pintype "bidirectional"))
    )
    (net (code "70") (name "unconnected-(U1-PB05{slash}ADC1-7-Pad6)") (class "Default")
      (node (ref "U1") (pin "6") (pinfunction "PB05/ADC1-7_6") (pintype "bidirectional"))
    )
    (net (code "71") (name "unconnected-(U1-PB10{slash}SER4-2{slash}TC5-0{slash}TCC0-4-Pad23)") (class "Default")
      (node (ref "U1") (pin "23") (pinfunction "PB10/SER4-2/TC5-0/TCC0-4_23") (pintype "bidirectional"))
    )
    (net (code "72") (name "unconnected-(U1-PB11{slash}SER4-3{slash}TC5-1{slash}TCC0-5-Pad24)") (class "Default")
      (node (ref "U1") (pin "24") (pinfunction "PB11/SER4-3/TC5-1/TCC0-5_24") (pintype "bidirectional"))
    )
    (net (code "73") (name "unconnected-(U1-PB12{slash}SER4-0{slash}TC4-0-Pad25)") (class "Default")
      (node (ref "U1") (pin "25") (pinfunction "PB12/SER4-0/TC4-0_25") (pintype "bidirectional"))
    )
    (net (code "74") (name "unconnected-(U1-PB15{slash}SER4-3{slash}TC5-1-Pad28)") (class "Default")
      (node (ref "U1") (pin "28") (pinfunction "PB15/SER4-3/TC5-1_28") (pintype "bidirectional"))
    )
    (net (code "75") (name "unconnected-(U1-PB16{slash}SER5-0{slash}TC6-0-Pad39)") (class "Default")
      (node (ref "U1") (pin "39") (pinfunction "PB16/SER5-0/TC6-0_39") (pintype "bidirectional"))
    )
    (net (code "76") (name "unconnected-(U1-PB17{slash}SER5-1{slash}TC6-1-Pad40)") (class "Default")
      (node (ref "U1") (pin "40") (pinfunction "PB17/SER5-1/TC6-1_40") (pintype "bidirectional"))
    )
    (net (code "77") (name "unconnected-(U1-PB22{slash}XIN1{slash}SER1-2{slash}SER5-2{slash}TC7-0-Pad49)") (class "Default")
      (node (ref "U1") (pin "49") (pinfunction "PB22/XIN1/SER1-2/SER5-2/TC7-0_49") (pintype "bidirectional"))
    )
    (net (code "78") (name "unconnected-(U1-PB23{slash}XOUT1{slash}SER1-3{slash}SER5-3{slash}TC7-1-Pad50)") (class "Default")
      (node (ref "U1") (pin "50") (pinfunction "PB23/XOUT1/SER1-3/SER5-3/TC7-1_50") (pintype "bidirectional"))
    )
    (net (code "79") (name "unconnected-(U1-PB31{slash}SER7-1{slash}SER5-0{slash}TC0-1-Pad60)") (class "Default")
      (node (ref "U1") (pin "60") (pinfunction "PB31/SER7-1/SER5-0/TC0-1_60") (pintype "bidirectional"))
    )
    (net (code "80") (name "unconnected-(U1-VSW-Pad55)") (class "Default")
      (node (ref "U1") (pin "55") (pinfunction "VSW_55") (pintype "bidirectional"))
    )
    (net (code "81") (name "unconnected-(U2-A-Pad1)") (class "Default")
      (node (ref "U2") (pin "1") (pinfunction "A_1") (pintype "bidirectional"))
    )
    (net (code "82") (name "unconnected-(U2-ALIGN-Pad7)") (class "Default")
      (node (ref "U2") (pin "7") (pinfunction "ALIGN_7") (pintype "bidirectional"))
    )
    (net (code "83") (name "unconnected-(U2-B-Pad2)") (class "Default")
      (node (ref "U2") (pin "2") (pinfunction "B_2") (pintype "bidirectional"))
    )
    (net (code "84") (name "unconnected-(U2-I-Pad3)") (class "Default")
      (node (ref "U2") (pin "3") (pinfunction "I_3") (pintype "bidirectional"))
    )
    (net (code "85") (name "unconnected-(U2-MAG_HI-Pad4)") (class "Default")
      (node (ref "U2") (pin "4") (pinfunction "MAG_HI_4") (pintype "bidirectional"))
    )
    (net (code "86") (name "unconnected-(U2-MAG_LO-Pad5)") (class "Default")
      (node (ref "U2") (pin "5") (pinfunction "MAG_LO_5") (pintype "bidirectional"))
    )
    (net (code "87") (name "unconnected-(U2-PROG-Pad13)") (class "Default")
      (node (ref "U2") (pin "13") (pinfunction "PROG_13") (pintype "bidirectional"))
    )
    (net (code "88") (name "unconnected-(U2-PWM-Pad8)") (class "Default")
      (node (ref "U2") (pin "8") (pinfunction "PWM_8") (pintype "bidirectional"))
    )
    (net (code "89") (name "unconnected-(U2-PWRDOWN-Pad11)") (class "Default")
      (node (ref "U2") (pin "11") (pinfunction "PWRDOWN_11") (pintype "bidirectional"))
    )
    (net (code "90") (name "unconnected-(U3-TEST_ANA-Pad37)") (class "Default")
      (node (ref "U3") (pin "37") (pinfunction "TEST_ANA_37") (pintype "bidirectional"))
    )
  )
)
